# untitled.net
KiCad netlist of a schematic drawn in EAGLE
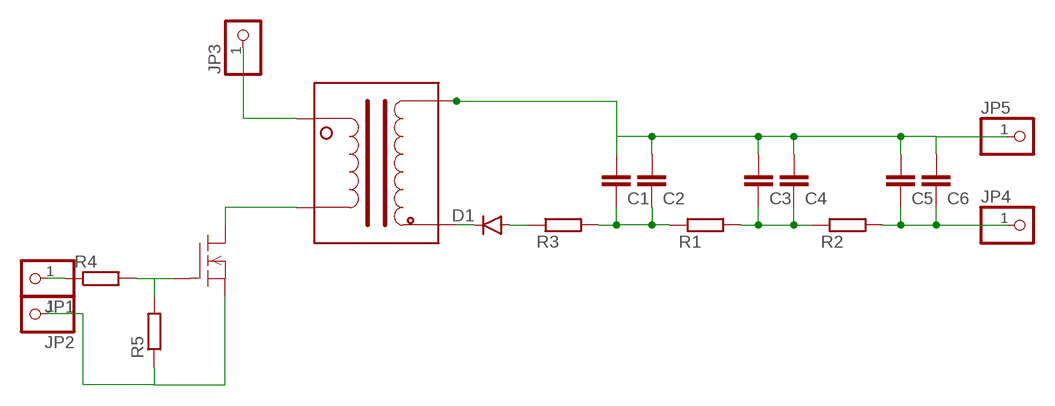
[diagram p0: schematic, sheet 1]

(export (version "E")
  (design (tool "Eeschema 10.0.6"))
  (components
    (comp (ref "C1")
      (value "CC1206")
      (footprint "eagle-import:C1206")
      (libsource (lib "eagle-import") (part "CC1206"))
    )
    (comp (ref "C2")
      (value "CC1206")
      (footprint "eagle-import:C1206")
      (libsource (lib "eagle-import") (part "CC1206"))
    )
    (comp (ref "C3")
      (value "CC1206")
      (footprint "eagle-import:C1206")
      (libsource (lib "eagle-import") (part "CC1206"))
    )
    (comp (ref "C4")
      (value "CC1206")
      (footprint "eagle-import:C1206")
      (libsource (lib "eagle-import") (part "CC1206"))
    )
    (comp (ref "C5")
      (value "CC1206")
      (footprint "eagle-import:C1206")
      (libsource (lib "eagle-import") (part "CC1206"))
    )
    (comp (ref "C6")
      (value "CC1206")
      (footprint "eagle-import:C1206")
      (libsource (lib "eagle-import") (part "CC1206"))
    )
    (comp (ref "D1")
      (value "DIODESMA")
      (footprint "eagle-import:SMA-DIODE")
      (libsource (lib "eagle-import") (part "DIODESMA"))
    )
    (comp (ref "JP1")
      (value "PINHD-1X01_2.54-90°")
      (footprint "eagle-import:1X01_90")
      (libsource (lib "eagle-import") (part "PINHD-1X01_2.54-90°"))
    )
    (comp (ref "JP2")
      (value "PINHD-1X01_2.54-90°")
      (footprint "eagle-import:1X01_90")
      (libsource (lib "eagle-import") (part "PINHD-1X01_2.54-90°"))
    )
    (comp (ref "JP3")
      (value "PINHD-1X01_2.54-90°")
      (footprint "eagle-import:1X01_90")
      (libsource (lib "eagle-import") (part "PINHD-1X01_2.54-90°"))
    )
    (comp (ref "JP4")
      (value "PINHD-1X01_2.54-90°")
      (footprint "eagle-import:1X01_90")
      (libsource (lib "eagle-import") (part "PINHD-1X01_2.54-90°"))
    )
    (comp (ref "JP5")
      (value "PINHD-1X01_2.54-90°")
      (footprint "eagle-import:1X01_90")
      (libsource (lib "eagle-import") (part "PINHD-1X01_2.54-90°"))
    )
    (comp (ref "R1")
      (value "R0805")
      (footprint "eagle-import:R0805")
      (libsource (lib "eagle-import") (part "R0805"))
    )
    (comp (ref "R2")
      (value "R0805")
      (footprint "eagle-import:R0805")
      (libsource (lib "eagle-import") (part "R0805"))
    )
    (comp (ref "R3")
      (value "R0805")
      (footprint "eagle-import:R0805")
      (libsource (lib "eagle-import") (part "R0805"))
    )
    (comp (ref "R4")
      (value "R0805")
      (footprint "eagle-import:R0805")
      (libsource (lib "eagle-import") (part "R0805"))
    )
    (comp (ref "R5")
      (value "R0805")
      (footprint "eagle-import:R0805")
      (libsource (lib "eagle-import") (part "R0805"))
    )
    (comp (ref "U$1")
      (value "TR1")
      (footprint "eagle-import:TR1")
      (libsource (lib "eagle-import") (part "TR1"))
    )
    (comp (ref "U$2")
      (value "AP9402GYT-HF")
      (footprint "eagle-import:SON-3X3")
      (libsource (lib "eagle-import") (part "AP9402GYT-HF"))
    )
  )
  (nets
    (net (code "1") (name "Net-(C1-Pad1)") (class "Default")
      (node (ref "C1") (pin "1") (pinfunction "1_1") (pintype "passive"))
      (node (ref "C2") (pin "1") (pinfunction "1_1") (pintype "passive"))
      (node (ref "R1") (pin "1") (pinfunction "1_1") (pintype "passive"))
      (node (ref "R3") (pin "2") (pinfunction "2_2") (pintype "passive"))
    )
    (net (code "2") (name "Net-(C3-Pad1)") (class "Default")
      (node (ref "C3") (pin "1") (pinfunction "1_1") (pintype "passive"))
      (node (ref "C4") (pin "1") (pinfunction "1_1") (pintype "passive"))
      (node (ref "R1") (pin "2") (pinfunction "2_2") (pintype "passive"))
      (node (ref "R2") (pin "1") (pinfunction "1_1") (pintype "passive"))
    )
    (net (code "3") (name "Net-(C5-Pad1)") (class "Default")
      (node (ref "C5") (pin "1") (pinfunction "1_1") (pintype "passive"))
      (node (ref "C6") (pin "1") (pinfunction "1_1") (pintype "passive"))
      (node (ref "JP4") (pin "1") (pinfunction "1_1") (pintype "passive"))
      (node (ref "R2") (pin "2") (pinfunction "2_2") (pintype "passive"))
    )
    (net (code "4") (name "Net-(D1-PadA)") (class "Default")
      (node (ref "D1") (pin "A") (pinfunction "A_A") (pintype "passive"))
      (node (ref "R3") (pin "1") (pinfunction "1_1") (pintype "passive"))
    )
    (net (code "5") (name "Net-(JP1-Pad1)") (class "Default")
      (node (ref "JP1") (pin "1") (pinfunction "1_1") (pintype "passive"))
      (node (ref "R4") (pin "1") (pinfunction "1_1") (pintype "passive"))
    )
    (net (code "6") (name "Net-(JP2-Pad1)") (class "Default")
      (node (ref "JP2") (pin "1") (pinfunction "1_1") (pintype "passive"))
      (node (ref "R5") (pin "1") (pinfunction "1_1") (pintype "passive"))
      (node (ref "U$2") (pin "1") (pinfunction "S_1") (pintype "bidirectional"))
      (node (ref "U$2") (pin "2") (pinfunction "S_2") (pintype "bidirectional"))
      (node (ref "U$2") (pin "3") (pinfunction "S_3") (pintype "bidirectional"))
    )
    (net (code "7") (name "Net-(U$1-IN1)") (class "Default")
      (node (ref "U$1") (pin "OUT1") (pinfunction "IN1_OUT1") (pintype "bidirectional"))
      (node (ref "U$2") (pin "5") (pinfunction "D_5") (pintype "bidirectional"))
      (node (ref "U$2") (pin "6") (pinfunction "D_6") (pintype "bidirectional"))
      (node (ref "U$2") (pin "7") (pinfunction "D_7") (pintype "bidirectional"))
      (node (ref "U$2") (pin "8") (pinfunction "D_8") (pintype "bidirectional"))
      (node (ref "U$2") (pin "9") (pinfunction "D_9") (pintype "bidirectional"))
    )
    (net (code "8") (name "Net-(U$1-IN2)") (class "Default")
      (node (ref "JP3") (pin "1") (pinfunction "1_1") (pintype "passive"))
      (node (ref "U$1") (pin "OUT2") (pinfunction "IN2_OUT2") (pintype "bidirectional"))
    )
    (net (code "9") (name "Net-(U$1-OUT1)") (class "Default")
      (node (ref "C1") (pin "2") (pinfunction "2_2") (pintype "passive"))
      (node (ref "C2") (pin "2") (pinfunction "2_2") (pintype "passive"))
      (node (ref "C3") (pin "2") (pinfunction "2_2") (pintype "passive"))
      (node (ref "C4") (pin "2") (pinfunction "2_2") (pintype "passive"))
      (node (ref "C5") (pin "2") (pinfunction "2_2") (pintype "passive"))
      (node (ref "C6") (pin "2") (pinfunction "2_2") (pintype "passive"))
      (node (ref "JP5") (pin "1") (pinfunction "1_1") (pintype "passive"))
      (node (ref "U$1") (pin "IN1") (pinfunction "OUT1_IN1") (pintype "bidirectional"))
    )
    (net (code "10") (name "Net-(U$1-OUT2)") (class "Default")
      (node (ref "D1") (pin "C") (pinfunction "C_C") (pintype "passive"))
      (node (ref "U$1") (pin "IN2") (pinfunction "OUT2_IN2") (pintype "bidirectional"))
    )
    (net (code "11") (name "Net-(U$2-G)") (class "Default")
      (node (ref "R4") (pin "2") (pinfunction "2_2") (pintype "passive"))
      (node (ref "R5") (pin "2") (pinfunction "2_2") (pintype "passive"))
      (node (ref "U$2") (pin "4") (pinfunction "G_4") (pintype "bidirectional"))
    )
  )
)
